# Scheme.net
KiCad netlist of a schematic drawn in Altium Designer
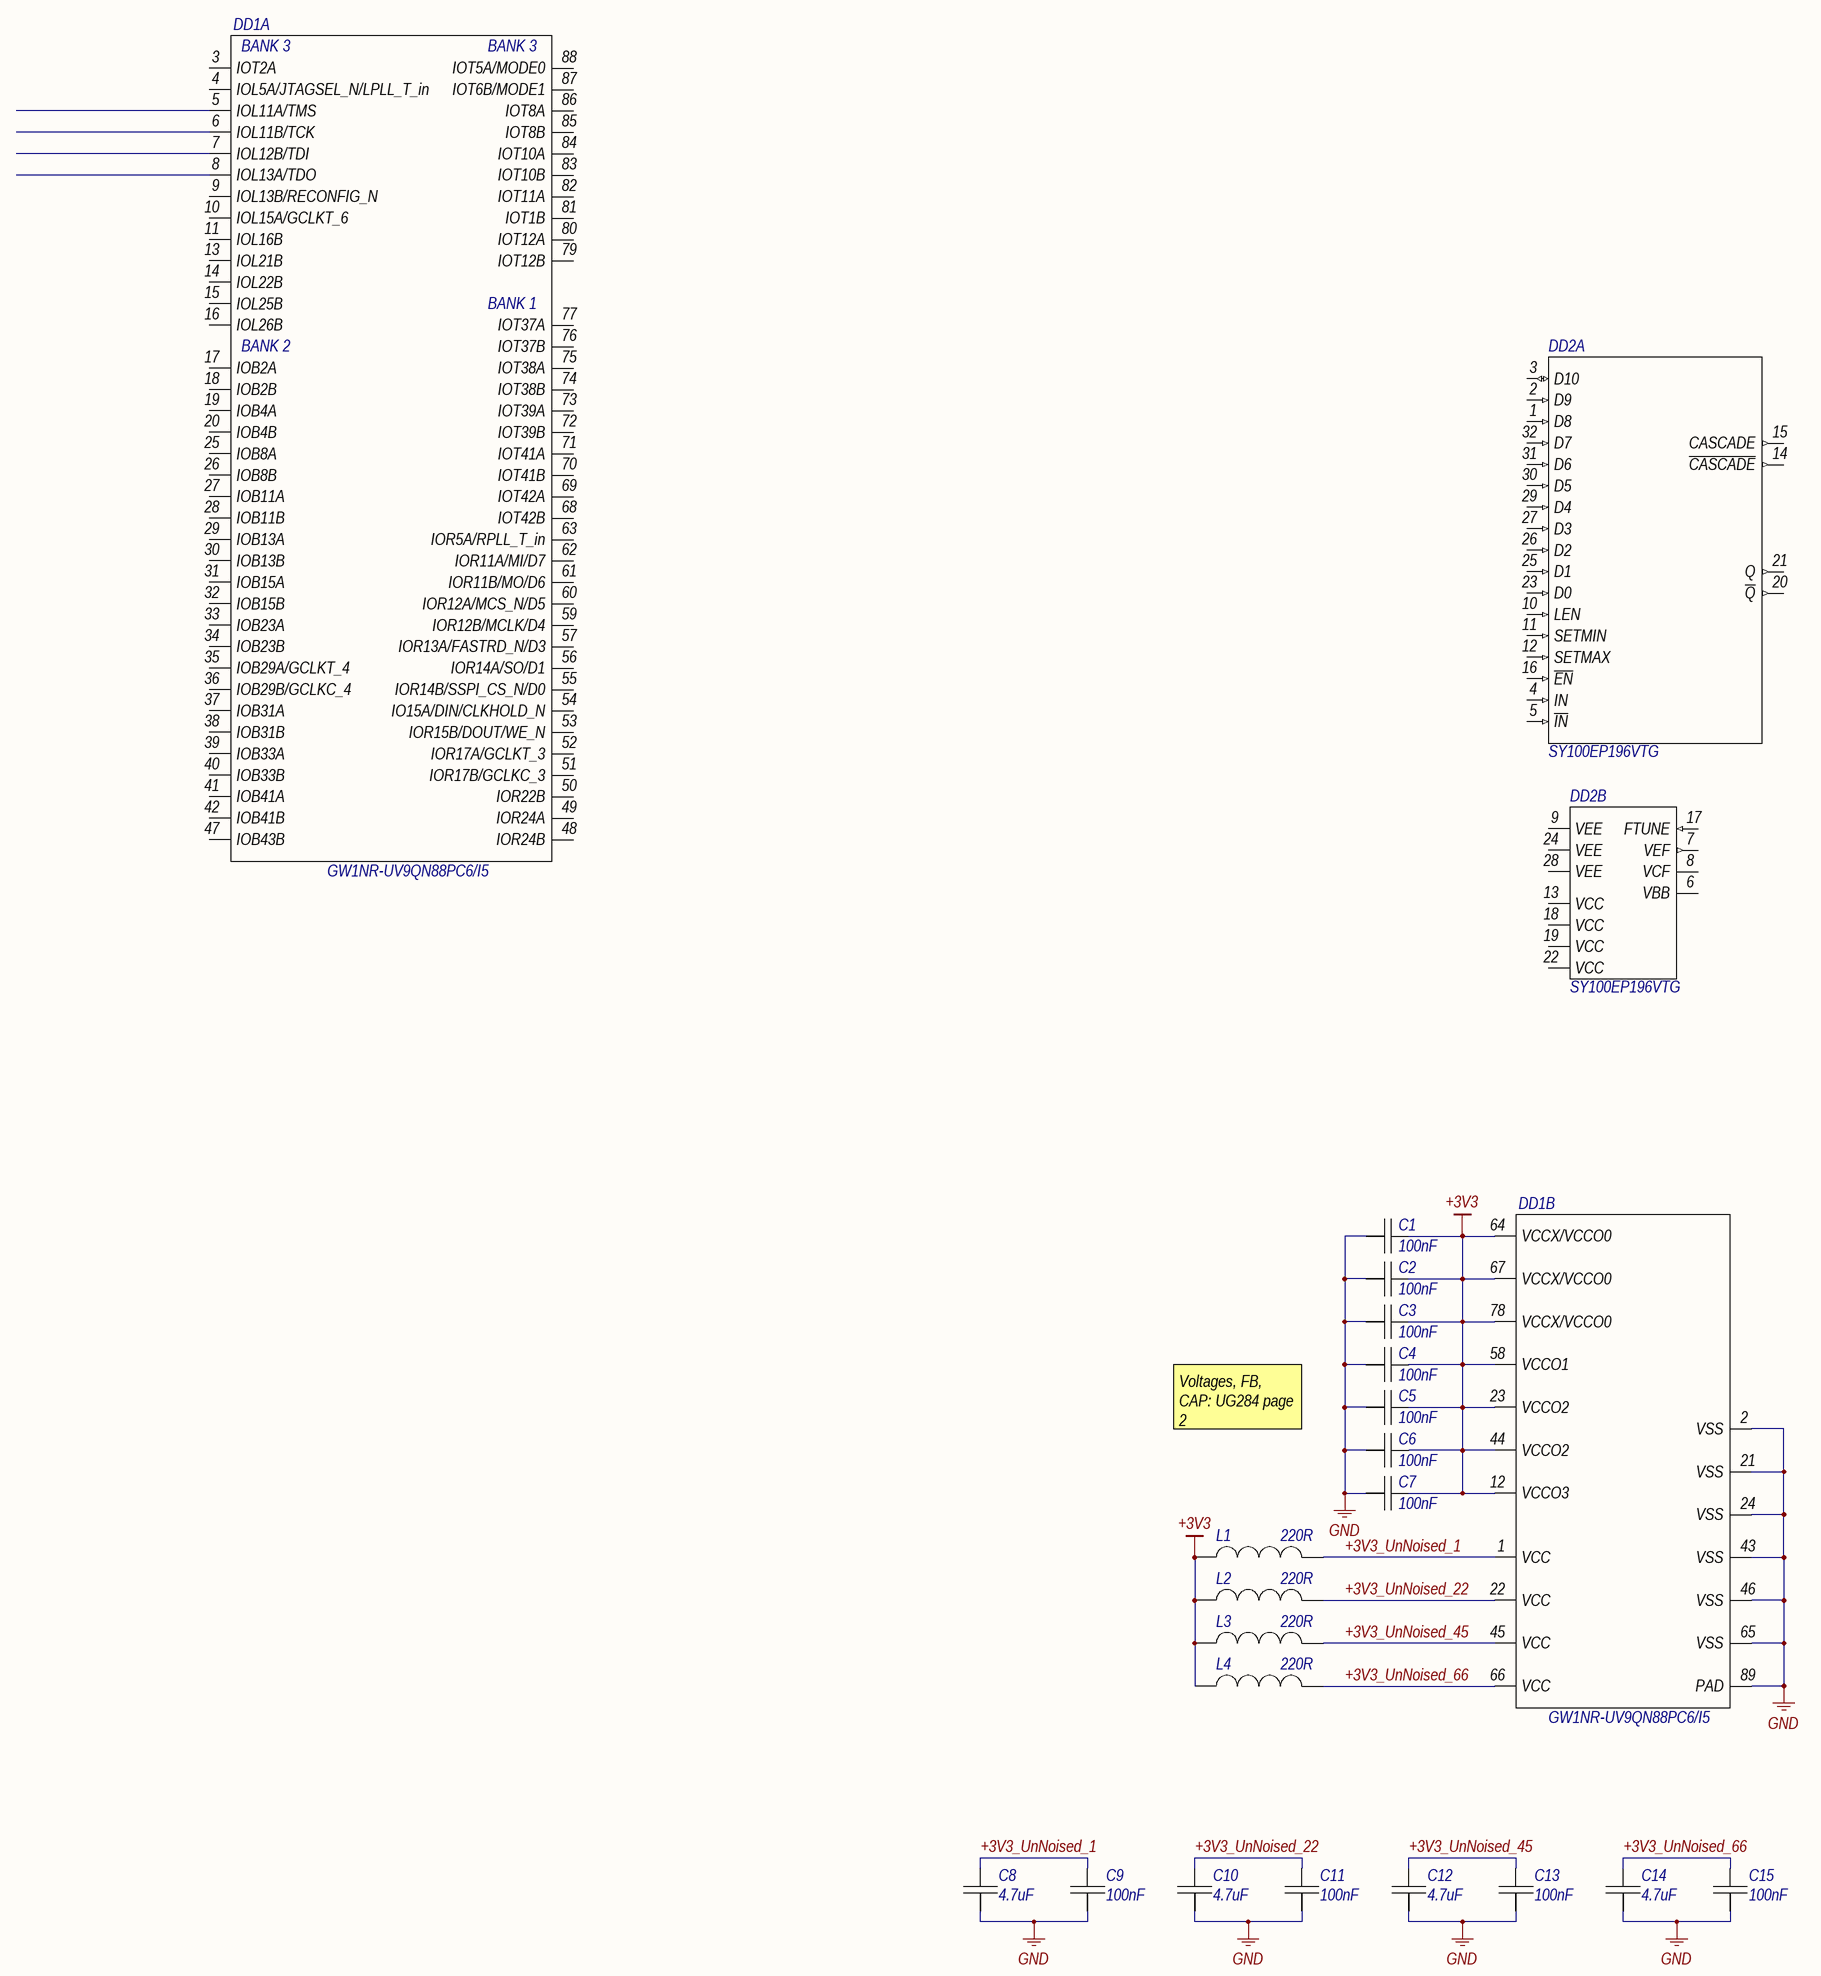
[diagram p0: Scheme.SchDoc]

(export (version "E")
  (design (tool "Eeschema 10.0.6"))
  (components
    (comp (ref "C1")
      (value "100nF")
      (footprint "CAP0402")
      (fields
        (field (name "MANUFACTURER") "Samsung Electro-Mechanics")
        (field (name "MPN") "CL05B104KO5NNNC")
        (field (name "TOLERANCE") "10%")
      )
      (libsource (lib "Library") (part "CAPC"))
    )
    (comp (ref "C2")
      (value "100nF")
      (footprint "CAP0402")
      (fields
        (field (name "MANUFACTURER") "Samsung Electro-Mechanics")
        (field (name "MPN") "CL05B104KO5NNNC")
        (field (name "TOLERANCE") "10%")
      )
      (libsource (lib "Library") (part "CAPC"))
    )
    (comp (ref "C3")
      (value "100nF")
      (footprint "CAP0402")
      (fields
        (field (name "MANUFACTURER") "Samsung Electro-Mechanics")
        (field (name "MPN") "CL05B104KO5NNNC")
        (field (name "TOLERANCE") "10%")
      )
      (libsource (lib "Library") (part "CAPC"))
    )
    (comp (ref "C4")
      (value "100nF")
      (footprint "CAP0402")
      (fields
        (field (name "MANUFACTURER") "Samsung Electro-Mechanics")
        (field (name "MPN") "CL05B104KO5NNNC")
        (field (name "TOLERANCE") "10%")
      )
      (libsource (lib "Library") (part "CAPC"))
    )
    (comp (ref "C5")
      (value "100nF")
      (footprint "CAP0402")
      (fields
        (field (name "MANUFACTURER") "Samsung Electro-Mechanics")
        (field (name "MPN") "CL05B104KO5NNNC")
        (field (name "TOLERANCE") "10%")
      )
      (libsource (lib "Library") (part "CAPC"))
    )
    (comp (ref "C6")
      (value "100nF")
      (footprint "CAP0402")
      (fields
        (field (name "MANUFACTURER") "Samsung Electro-Mechanics")
        (field (name "MPN") "CL05B104KO5NNNC")
        (field (name "TOLERANCE") "10%")
      )
      (libsource (lib "Library") (part "CAPC"))
    )
    (comp (ref "C7")
      (value "100nF")
      (footprint "CAP0402")
      (fields
        (field (name "MANUFACTURER") "Samsung Electro-Mechanics")
        (field (name "MPN") "CL05B104KO5NNNC")
        (field (name "TOLERANCE") "10%")
      )
      (libsource (lib "Library") (part "CAPC"))
    )
    (comp (ref "C8")
      (value "4.7uF")
      (footprint "CAP0402")
      (fields
        (field (name "MANUFACTURER") "Samsung Electro-Mechanics")
        (field (name "MPN") "CL05A475MP5NRNC")
        (field (name "TOLERANCE") "20%")
      )
      (libsource (lib "Library") (part "CAPC"))
    )
    (comp (ref "C9")
      (value "100nF")
      (footprint "CAP0402")
      (fields
        (field (name "MANUFACTURER") "Samsung Electro-Mechanics")
        (field (name "MPN") "CL05B104KO5NNNC")
        (field (name "TOLERANCE") "10%")
      )
      (libsource (lib "Library") (part "CAPC"))
    )
    (comp (ref "C10")
      (value "4.7uF")
      (footprint "CAP0402")
      (fields
        (field (name "MANUFACTURER") "Samsung Electro-Mechanics")
        (field (name "MPN") "CL05A475MP5NRNC")
        (field (name "TOLERANCE") "20%")
      )
      (libsource (lib "Library") (part "CAPC"))
    )
    (comp (ref "C11")
      (value "100nF")
      (footprint "CAP0402")
      (fields
        (field (name "MANUFACTURER") "Samsung Electro-Mechanics")
        (field (name "MPN") "CL05B104KO5NNNC")
        (field (name "TOLERANCE") "10%")
      )
      (libsource (lib "Library") (part "CAPC"))
    )
    (comp (ref "C12")
      (value "4.7uF")
      (footprint "CAP0402")
      (fields
        (field (name "MANUFACTURER") "Samsung Electro-Mechanics")
        (field (name "MPN") "CL05A475MP5NRNC")
        (field (name "TOLERANCE") "20%")
      )
      (libsource (lib "Library") (part "CAPC"))
    )
    (comp (ref "C13")
      (value "100nF")
      (footprint "CAP0402")
      (fields
        (field (name "MANUFACTURER") "Samsung Electro-Mechanics")
        (field (name "MPN") "CL05B104KO5NNNC")
        (field (name "TOLERANCE") "10%")
      )
      (libsource (lib "Library") (part "CAPC"))
    )
    (comp (ref "C14")
      (value "4.7uF")
      (footprint "CAP0402")
      (fields
        (field (name "MANUFACTURER") "Samsung Electro-Mechanics")
        (field (name "MPN") "CL05A475MP5NRNC")
        (field (name "TOLERANCE") "20%")
      )
      (libsource (lib "Library") (part "CAPC"))
    )
    (comp (ref "C15")
      (value "100nF")
      (footprint "CAP0402")
      (fields
        (field (name "MANUFACTURER") "Samsung Electro-Mechanics")
        (field (name "MPN") "CL05B104KO5NNNC")
        (field (name "TOLERANCE") "10%")
      )
      (libsource (lib "Library") (part "CAPC"))
    )
    (comp (ref "DD1")
      (value "GW1NR-UV9QN88PC6/I5")
      (footprint "QFN88_0.4pitch")
      (fields (field (name "MPN") "GW1NR-UV9QN88PC6/I5") (field (name "MANUFACTURER") "GoWin"))
      (libsource (lib "Library") (part "DD_GW1NR-UV9QN88PC6/I5"))
    )
    (comp (ref "DD2")
      (value "~")
      (footprint "TQFP-32_M")
      (fields
        (field (name "MPN") "SY100EP196VTG")
        (field (name "PART NUMBER") "SY100EP196VTG")
        (field (name "MANUFACTURER") "Microchip")
      )
      (libsource (lib "Library") (part "SY100EP196VTG"))
    )
    (comp (ref "L1")
      (value "220R")
      (footprint "CAPC0603N")
      (fields
        (field (name "MANUFACTURER") "Murata Electronics")
        (field (name "MPN") "BLM18KG221SN1D")
        (field (name "TOLERANCE") "25%")
      )
      (libsource (lib "Library") (part "Inductor"))
    )
    (comp (ref "L2")
      (value "220R")
      (footprint "CAPC0603N")
      (fields
        (field (name "MANUFACTURER") "Murata Electronics")
        (field (name "MPN") "BLM18KG221SN1D")
        (field (name "TOLERANCE") "25%")
      )
      (libsource (lib "Library") (part "Inductor"))
    )
    (comp (ref "L3")
      (value "220R")
      (footprint "CAPC0603N")
      (fields
        (field (name "MANUFACTURER") "Murata Electronics")
        (field (name "MPN") "BLM18KG221SN1D")
        (field (name "TOLERANCE") "25%")
      )
      (libsource (lib "Library") (part "Inductor"))
    )
    (comp (ref "L4")
      (value "220R")
      (footprint "CAPC0603N")
      (fields
        (field (name "MANUFACTURER") "Murata Electronics")
        (field (name "MPN") "BLM18KG221SN1D")
        (field (name "TOLERANCE") "25%")
      )
      (libsource (lib "Library") (part "Inductor"))
    )
  )
  (nets
    (net (code "1") (name "+3V3") (class "Default")
      (node (ref "C1") (pin "2") (pinfunction "2_2") (pintype "passive"))
      (node (ref "C2") (pin "2") (pinfunction "2_2") (pintype "passive"))
      (node (ref "C3") (pin "2") (pinfunction "2_2") (pintype "passive"))
      (node (ref "C4") (pin "2") (pinfunction "2_2") (pintype "passive"))
      (node (ref "C5") (pin "2") (pinfunction "2_2") (pintype "passive"))
      (node (ref "C6") (pin "2") (pinfunction "2_2") (pintype "passive"))
      (node (ref "C7") (pin "2") (pinfunction "2_2") (pintype "passive"))
      (node (ref "DD1") (pin "12") (pinfunction "VCCO3_12") (pintype "power_in"))
      (node (ref "DD1") (pin "23") (pinfunction "VCCO2_23") (pintype "power_in"))
      (node (ref "DD1") (pin "44") (pinfunction "VCCO2_44") (pintype "power_in"))
      (node (ref "DD1") (pin "58") (pinfunction "VCCO1_58") (pintype "power_in"))
      (node (ref "DD1") (pin "64") (pinfunction "VCCX/VCCO0_64") (pintype "power_in"))
      (node (ref "DD1") (pin "67") (pinfunction "VCCX/VCCO0_67") (pintype "power_in"))
      (node (ref "DD1") (pin "78") (pinfunction "VCCX/VCCO0_78") (pintype "power_in"))
      (node (ref "L1") (pin "1") (pinfunction "1_1") (pintype "passive"))
      (node (ref "L2") (pin "1") (pinfunction "1_1") (pintype "passive"))
      (node (ref "L3") (pin "1") (pinfunction "1_1") (pintype "passive"))
      (node (ref "L4") (pin "1") (pinfunction "1_1") (pintype "passive"))
    )
    (net (code "2") (name "/+3V3_UnNoised_1") (class "Default")
      (node (ref "C8") (pin "2") (pinfunction "2_2") (pintype "passive"))
      (node (ref "C9") (pin "2") (pinfunction "2_2") (pintype "passive"))
      (node (ref "DD1") (pin "1") (pinfunction "VCC_1") (pintype "power_in"))
      (node (ref "L1") (pin "2") (pinfunction "2_2") (pintype "passive"))
    )
    (net (code "3") (name "/+3V3_UnNoised_22") (class "Default")
      (node (ref "C10") (pin "2") (pinfunction "2_2") (pintype "passive"))
      (node (ref "C11") (pin "2") (pinfunction "2_2") (pintype "passive"))
      (node (ref "DD1") (pin "22") (pinfunction "VCC_22") (pintype "power_in"))
      (node (ref "L2") (pin "2") (pinfunction "2_2") (pintype "passive"))
    )
    (net (code "4") (name "/+3V3_UnNoised_45") (class "Default")
      (node (ref "C12") (pin "2") (pinfunction "2_2") (pintype "passive"))
      (node (ref "C13") (pin "2") (pinfunction "2_2") (pintype "passive"))
      (node (ref "DD1") (pin "45") (pinfunction "VCC_45") (pintype "power_in"))
      (node (ref "L3") (pin "2") (pinfunction "2_2") (pintype "passive"))
    )
    (net (code "5") (name "/+3V3_UnNoised_66") (class "Default")
      (node (ref "C14") (pin "2") (pinfunction "2_2") (pintype "passive"))
      (node (ref "C15") (pin "2") (pinfunction "2_2") (pintype "passive"))
      (node (ref "DD1") (pin "66") (pinfunction "VCC_66") (pintype "power_in"))
      (node (ref "L4") (pin "2") (pinfunction "2_2") (pintype "passive"))
    )
    (net (code "6") (name "GND") (class "Default")
      (node (ref "C1") (pin "1") (pinfunction "1_1") (pintype "passive"))
      (node (ref "C10") (pin "1") (pinfunction "1_1") (pintype "passive"))
      (node (ref "C11") (pin "1") (pinfunction "1_1") (pintype "passive"))
      (node (ref "C12") (pin "1") (pinfunction "1_1") (pintype "passive"))
      (node (ref "C13") (pin "1") (pinfunction "1_1") (pintype "passive"))
      (node (ref "C14") (pin "1") (pinfunction "1_1") (pintype "passive"))
      (node (ref "C15") (pin "1") (pinfunction "1_1") (pintype "passive"))
      (node (ref "C2") (pin "1") (pinfunction "1_1") (pintype "passive"))
      (node (ref "C3") (pin "1") (pinfunction "1_1") (pintype "passive"))
      (node (ref "C4") (pin "1") (pinfunction "1_1") (pintype "passive"))
      (node (ref "C5") (pin "1") (pinfunction "1_1") (pintype "passive"))
      (node (ref "C6") (pin "1") (pinfunction "1_1") (pintype "passive"))
      (node (ref "C7") (pin "1") (pinfunction "1_1") (pintype "passive"))
      (node (ref "C8") (pin "1") (pinfunction "1_1") (pintype "passive"))
      (node (ref "C9") (pin "1") (pinfunction "1_1") (pintype "passive"))
      (node (ref "DD1") (pin "2") (pinfunction "VSS_2") (pintype "power_in"))
      (node (ref "DD1") (pin "21") (pinfunction "VSS_21") (pintype "power_in"))
      (node (ref "DD1") (pin "24") (pinfunction "VSS_24") (pintype "power_in"))
      (node (ref "DD1") (pin "43") (pinfunction "VSS_43") (pintype "power_in"))
      (node (ref "DD1") (pin "46") (pinfunction "VSS_46") (pintype "power_in"))
      (node (ref "DD1") (pin "65") (pinfunction "VSS_65") (pintype "power_in"))
      (node (ref "DD1") (pin "89") (pinfunction "PAD_89") (pintype "passive"))
    )
    (net (code "7") (name "unconnected-(DD1A-IO15A{slash}DIN{slash}CLKHOLD_N-Pad54)") (class "Default")
      (node (ref "DD1") (pin "54") (pinfunction "IO15A/DIN/CLKHOLD_N_54") (pintype "passive"))
    )
    (net (code "8") (name "unconnected-(DD1A-IOB2A-Pad17)") (class "Default")
      (node (ref "DD1") (pin "17") (pinfunction "IOB2A_17") (pintype "passive"))
    )
    (net (code "9") (name "unconnected-(DD1A-IOB2B-Pad18)") (class "Default")
      (node (ref "DD1") (pin "18") (pinfunction "IOB2B_18") (pintype "passive"))
    )
    (net (code "10") (name "unconnected-(DD1A-IOB4A-Pad19)") (class "Default")
      (node (ref "DD1") (pin "19") (pinfunction "IOB4A_19") (pintype "passive"))
    )
    (net (code "11") (name "unconnected-(DD1A-IOB4B-Pad20)") (class "Default")
      (node (ref "DD1") (pin "20") (pinfunction "IOB4B_20") (pintype "passive"))
    )
    (net (code "12") (name "unconnected-(DD1A-IOB8A-Pad25)") (class "Default")
      (node (ref "DD1") (pin "25") (pinfunction "IOB8A_25") (pintype "passive"))
    )
    (net (code "13") (name "unconnected-(DD1A-IOB8B-Pad26)") (class "Default")
      (node (ref "DD1") (pin "26") (pinfunction "IOB8B_26") (pintype "passive"))
    )
    (net (code "14") (name "unconnected-(DD1A-IOB11A-Pad27)") (class "Default")
      (node (ref "DD1") (pin "27") (pinfunction "IOB11A_27") (pintype "passive"))
    )
    (net (code "15") (name "unconnected-(DD1A-IOB11B-Pad28)") (class "Default")
      (node (ref "DD1") (pin "28") (pinfunction "IOB11B_28") (pintype "passive"))
    )
    (net (code "16") (name "unconnected-(DD1A-IOB13A-Pad29)") (class "Default")
      (node (ref "DD1") (pin "29") (pinfunction "IOB13A_29") (pintype "passive"))
    )
    (net (code "17") (name "unconnected-(DD1A-IOB13B-Pad30)") (class "Default")
      (node (ref "DD1") (pin "30") (pinfunction "IOB13B_30") (pintype "passive"))
    )
    (net (code "18") (name "unconnected-(DD1A-IOB15A-Pad31)") (class "Default")
      (node (ref "DD1") (pin "31") (pinfunction "IOB15A_31") (pintype "passive"))
    )
    (net (code "19") (name "unconnected-(DD1A-IOB15B-Pad32)") (class "Default")
      (node (ref "DD1") (pin "32") (pinfunction "IOB15B_32") (pintype "passive"))
    )
    (net (code "20") (name "unconnected-(DD1A-IOB23A-Pad33)") (class "Default")
      (node (ref "DD1") (pin "33") (pinfunction "IOB23A_33") (pintype "passive"))
    )
    (net (code "21") (name "unconnected-(DD1A-IOB23B-Pad34)") (class "Default")
      (node (ref "DD1") (pin "34") (pinfunction "IOB23B_34") (pintype "passive"))
    )
    (net (code "22") (name "unconnected-(DD1A-IOB29A{slash}GCLKT_4-Pad35)") (class "Default")
      (node (ref "DD1") (pin "35") (pinfunction "IOB29A/GCLKT_4_35") (pintype "passive"))
    )
    (net (code "23") (name "unconnected-(DD1A-IOB29B{slash}GCLKC_4-Pad36)") (class "Default")
      (node (ref "DD1") (pin "36") (pinfunction "IOB29B/GCLKC_4_36") (pintype "passive"))
    )
    (net (code "24") (name "unconnected-(DD1A-IOB31A-Pad37)") (class "Default")
      (node (ref "DD1") (pin "37") (pinfunction "IOB31A_37") (pintype "passive"))
    )
    (net (code "25") (name "unconnected-(DD1A-IOB31B-Pad38)") (class "Default")
      (node (ref "DD1") (pin "38") (pinfunction "IOB31B_38") (pintype "passive"))
    )
    (net (code "26") (name "unconnected-(DD1A-IOB33A-Pad39)") (class "Default")
      (node (ref "DD1") (pin "39") (pinfunction "IOB33A_39") (pintype "passive"))
    )
    (net (code "27") (name "unconnected-(DD1A-IOB33B-Pad40)") (class "Default")
      (node (ref "DD1") (pin "40") (pinfunction "IOB33B_40") (pintype "passive"))
    )
    (net (code "28") (name "unconnected-(DD1A-IOB41A-Pad41)") (class "Default")
      (node (ref "DD1") (pin "41") (pinfunction "IOB41A_41") (pintype "passive"))
    )
    (net (code "29") (name "unconnected-(DD1A-IOB41B-Pad42)") (class "Default")
      (node (ref "DD1") (pin "42") (pinfunction "IOB41B_42") (pintype "passive"))
    )
    (net (code "30") (name "unconnected-(DD1A-IOB43B-Pad47)") (class "Default")
      (node (ref "DD1") (pin "47") (pinfunction "IOB43B_47") (pintype "passive"))
    )
    (net (code "31") (name "unconnected-(DD1A-IOL5A{slash}JTAGSEL_N{slash}LPLL_T_in-Pad4)") (class "Default")
      (node (ref "DD1") (pin "4") (pinfunction "IOL5A/JTAGSEL_N/LPLL_T_in_4") (pintype "passive"))
    )
    (net (code "32") (name "unconnected-(DD1A-IOL11A{slash}TMS-Pad5)") (class "Default")
      (node (ref "DD1") (pin "5") (pinfunction "IOL11A/TMS_5") (pintype "passive"))
    )
    (net (code "33") (name "unconnected-(DD1A-IOL11B{slash}TCK-Pad6)") (class "Default")
      (node (ref "DD1") (pin "6") (pinfunction "IOL11B/TCK_6") (pintype "passive"))
    )
    (net (code "34") (name "unconnected-(DD1A-IOL12B{slash}TDI-Pad7)") (class "Default")
      (node (ref "DD1") (pin "7") (pinfunction "IOL12B/TDI_7") (pintype "passive"))
    )
    (net (code "35") (name "unconnected-(DD1A-IOL13A{slash}TDO-Pad8)") (class "Default")
      (node (ref "DD1") (pin "8") (pinfunction "IOL13A/TDO_8") (pintype "passive"))
    )
    (net (code "36") (name "unconnected-(DD1A-IOL13B{slash}RECONFIG_N-Pad9)") (class "Default")
      (node (ref "DD1") (pin "9") (pinfunction "IOL13B/RECONFIG_N_9") (pintype "passive"))
    )
    (net (code "37") (name "unconnected-(DD1A-IOL15A{slash}GCLKT_6-Pad10)") (class "Default")
      (node (ref "DD1") (pin "10") (pinfunction "IOL15A/GCLKT_6_10") (pintype "passive"))
    )
    (net (code "38") (name "unconnected-(DD1A-IOL16B-Pad11)") (class "Default")
      (node (ref "DD1") (pin "11") (pinfunction "IOL16B_11") (pintype "passive"))
    )
    (net (code "39") (name "unconnected-(DD1A-IOL21B-Pad13)") (class "Default")
      (node (ref "DD1") (pin "13") (pinfunction "IOL21B_13") (pintype "passive"))
    )
    (net (code "40") (name "unconnected-(DD1A-IOL22B-Pad14)") (class "Default")
      (node (ref "DD1") (pin "14") (pinfunction "IOL22B_14") (pintype "passive"))
    )
    (net (code "41") (name "unconnected-(DD1A-IOL25B-Pad15)") (class "Default")
      (node (ref "DD1") (pin "15") (pinfunction "IOL25B_15") (pintype "passive"))
    )
    (net (code "42") (name "unconnected-(DD1A-IOL26B-Pad16)") (class "Default")
      (node (ref "DD1") (pin "16") (pinfunction "IOL26B_16") (pintype "passive"))
    )
    (net (code "43") (name "unconnected-(DD1A-IOR5A{slash}RPLL_T_in-Pad63)") (class "Default")
      (node (ref "DD1") (pin "63") (pinfunction "IOR5A/RPLL_T_in_63") (pintype "passive"))
    )
    (net (code "44") (name "unconnected-(DD1A-IOR11A{slash}MI{slash}D7-Pad62)") (class "Default")
      (node (ref "DD1") (pin "62") (pinfunction "IOR11A/MI/D7_62") (pintype "passive"))
    )
    (net (code "45") (name "unconnected-(DD1A-IOR11B{slash}MO{slash}D6-Pad61)") (class "Default")
      (node (ref "DD1") (pin "61") (pinfunction "IOR11B/MO/D6_61") (pintype "passive"))
    )
    (net (code "46") (name "unconnected-(DD1A-IOR12A{slash}MCS_N{slash}D5-Pad60)") (class "Default")
      (node (ref "DD1") (pin "60") (pinfunction "IOR12A/MCS_N/D5_60") (pintype "passive"))
    )
    (net (code "47") (name "unconnected-(DD1A-IOR12B{slash}MCLK{slash}D4-Pad59)") (class "Default")
      (node (ref "DD1") (pin "59") (pinfunction "IOR12B/MCLK/D4_59") (pintype "passive"))
    )
    (net (code "48") (name "unconnected-(DD1A-IOR13A{slash}FASTRD_N{slash}D3-Pad57)") (class "Default")
      (node (ref "DD1") (pin "57") (pinfunction "IOR13A/FASTRD_N/D3_57") (pintype "passive"))
    )
    (net (code "49") (name "unconnected-(DD1A-IOR14A{slash}SO{slash}D1-Pad56)") (class "Default")
      (node (ref "DD1") (pin "56") (pinfunction "IOR14A/SO/D1_56") (pintype "passive"))
    )
    (net (code "50") (name "unconnected-(DD1A-IOR14B{slash}SSPI_CS_N{slash}D0-Pad55)") (class "Default")
      (node (ref "DD1") (pin "55") (pinfunction "IOR14B/SSPI_CS_N/D0_55") (pintype "passive"))
    )
    (net (code "51") (name "unconnected-(DD1A-IOR15B{slash}DOUT{slash}WE_N-Pad53)") (class "Default")
      (node (ref "DD1") (pin "53") (pinfunction "IOR15B/DOUT/WE_N_53") (pintype "passive"))
    )
    (net (code "52") (name "unconnected-(DD1A-IOR17A{slash}GCLKT_3-Pad52)") (class "Default")
      (node (ref "DD1") (pin "52") (pinfunction "IOR17A/GCLKT_3_52") (pintype "passive"))
    )
    (net (code "53") (name "unconnected-(DD1A-IOR17B{slash}GCLKC_3-Pad51)") (class "Default")
      (node (ref "DD1") (pin "51") (pinfunction "IOR17B/GCLKC_3_51") (pintype "passive"))
    )
    (net (code "54") (name "unconnected-(DD1A-IOR22B-Pad50)") (class "Default")
      (node (ref "DD1") (pin "50") (pinfunction "IOR22B_50") (pintype "passive"))
    )
    (net (code "55") (name "unconnected-(DD1A-IOR24A-Pad49)") (class "Default")
      (node (ref "DD1") (pin "49") (pinfunction "IOR24A_49") (pintype "passive"))
    )
    (net (code "56") (name "unconnected-(DD1A-IOR24B-Pad48)") (class "Default")
      (node (ref "DD1") (pin "48") (pinfunction "IOR24B_48") (pintype "passive"))
    )
    (net (code "57") (name "unconnected-(DD1A-IOT1B-Pad81)") (class "Default")
      (node (ref "DD1") (pin "81") (pinfunction "IOT1B_81") (pintype "passive"))
    )
    (net (code "58") (name "unconnected-(DD1A-IOT2A-Pad3)") (class "Default")
      (node (ref "DD1") (pin "3") (pinfunction "IOT2A_3") (pintype "passive"))
    )
    (net (code "59") (name "unconnected-(DD1A-IOT5A{slash}MODE0-Pad88)") (class "Default")
      (node (ref "DD1") (pin "88") (pinfunction "IOT5A/MODE0_88") (pintype "passive"))
    )
    (net (code "60") (name "unconnected-(DD1A-IOT6B{slash}MODE1-Pad87)") (class "Default")
      (node (ref "DD1") (pin "87") (pinfunction "IOT6B/MODE1_87") (pintype "passive"))
    )
    (net (code "61") (name "unconnected-(DD1A-IOT8A-Pad86)") (class "Default")
      (node (ref "DD1") (pin "86") (pinfunction "IOT8A_86") (pintype "passive"))
    )
    (net (code "62") (name "unconnected-(DD1A-IOT8B-Pad85)") (class "Default")
      (node (ref "DD1") (pin "85") (pinfunction "IOT8B_85") (pintype "passive"))
    )
    (net (code "63") (name "unconnected-(DD1A-IOT10A-Pad84)") (class "Default")
      (node (ref "DD1") (pin "84") (pinfunction "IOT10A_84") (pintype "passive"))
    )
    (net (code "64") (name "unconnected-(DD1A-IOT10B-Pad83)") (class "Default")
      (node (ref "DD1") (pin "83") (pinfunction "IOT10B_83") (pintype "passive"))
    )
    (net (code "65") (name "unconnected-(DD1A-IOT11A-Pad82)") (class "Default")
      (node (ref "DD1") (pin "82") (pinfunction "IOT11A_82") (pintype "passive"))
    )
    (net (code "66") (name "unconnected-(DD1A-IOT12A-Pad80)") (class "Default")
      (node (ref "DD1") (pin "80") (pinfunction "IOT12A_80") (pintype "passive"))
    )
    (net (code "67") (name "unconnected-(DD1A-IOT12B-Pad79)") (class "Default")
      (node (ref "DD1") (pin "79") (pinfunction "IOT12B_79") (pintype "passive"))
    )
    (net (code "68") (name "unconnected-(DD1A-IOT37A-Pad77)") (class "Default")
      (node (ref "DD1") (pin "77") (pinfunction "IOT37A_77") (pintype "passive"))
    )
    (net (code "69") (name "unconnected-(DD1A-IOT37B-Pad76)") (class "Default")
      (node (ref "DD1") (pin "76") (pinfunction "IOT37B_76") (pintype "passive"))
    )
    (net (code "70") (name "unconnected-(DD1A-IOT38A-Pad75)") (class "Default")
      (node (ref "DD1") (pin "75") (pinfunction "IOT38A_75") (pintype "passive"))
    )
    (net (code "71") (name "unconnected-(DD1A-IOT38B-Pad74)") (class "Default")
      (node (ref "DD1") (pin "74") (pinfunction "IOT38B_74") (pintype "passive"))
    )
    (net (code "72") (name "unconnected-(DD1A-IOT39A-Pad73)") (class "Default")
      (node (ref "DD1") (pin "73") (pinfunction "IOT39A_73") (pintype "passive"))
    )
    (net (code "73") (name "unconnected-(DD1A-IOT39B-Pad72)") (class "Default")
      (node (ref "DD1") (pin "72") (pinfunction "IOT39B_72") (pintype "passive"))
    )
    (net (code "74") (name "unconnected-(DD1A-IOT41A-Pad71)") (class "Default")
      (node (ref "DD1") (pin "71") (pinfunction "IOT41A_71") (pintype "passive"))
    )
    (net (code "75") (name "unconnected-(DD1A-IOT41B-Pad70)") (class "Default")
      (node (ref "DD1") (pin "70") (pinfunction "IOT41B_70") (pintype "passive"))
    )
    (net (code "76") (name "unconnected-(DD1A-IOT42A-Pad69)") (class "Default")
      (node (ref "DD1") (pin "69") (pinfunction "IOT42A_69") (pintype "passive"))
    )
    (net (code "77") (name "unconnected-(DD1A-IOT42B-Pad68)") (class "Default")
      (node (ref "DD1") (pin "68") (pinfunction "IOT42B_68") (pintype "passive"))
    )
    (net (code "78") (name "unconnected-(DD2A-CASCADE-Pad15)") (class "Default")
      (node (ref "DD2") (pin "15") (pinfunction "CASCADE_15") (pintype "output"))
    )
    (net (code "79") (name "unconnected-(DD2A-D0-Pad23)") (class "Default")
      (node (ref "DD2") (pin "23") (pinfunction "D0_23") (pintype "input"))
    )
    (net (code "80") (name "unconnected-(DD2A-D1-Pad25)") (class "Default")
      (node (ref "DD2") (pin "25") (pinfunction "D1_25") (pintype "input"))
    )
    (net (code "81") (name "unconnected-(DD2A-D2-Pad26)") (class "Default")
      (node (ref "DD2") (pin "26") (pinfunction "D2_26") (pintype "input"))
    )
    (net (code "82") (name "unconnected-(DD2A-D3-Pad27)") (class "Default")
      (node (ref "DD2") (pin "27") (pinfunction "D3_27") (pintype "input"))
    )
    (net (code "83") (name "unconnected-(DD2A-D4-Pad29)") (class "Default")
      (node (ref "DD2") (pin "29") (pinfunction "D4_29") (pintype "input"))
    )
    (net (code "84") (name "unconnected-(DD2A-D5-Pad30)") (class "Default")
      (node (ref "DD2") (pin "30") (pinfunction "D5_30") (pintype "input"))
    )
    (net (code "85") (name "unconnected-(DD2A-D6-Pad31)") (class "Default")
      (node (ref "DD2") (pin "31") (pinfunction "D6_31") (pintype "input"))
    )
    (net (code "86") (name "unconnected-(DD2A-D7-Pad32)") (class "Default")
      (node (ref "DD2") (pin "32") (pinfunction "D7_32") (pintype "input"))
    )
    (net (code "87") (name "unconnected-(DD2A-D8-Pad1)") (class "Default")
      (node (ref "DD2") (pin "1") (pinfunction "D8_1") (pintype "input"))
    )
    (net (code "88") (name "unconnected-(DD2A-D9-Pad2)") (class "Default")
      (node (ref "DD2") (pin "2") (pinfunction "D9_2") (pintype "input"))
    )
    (net (code "89") (name "unconnected-(DD2A-D10-Pad3)") (class "Default")
      (node (ref "DD2") (pin "3") (pinfunction "D10_3") (pintype "bidirectional"))
    )
    (net (code "90") (name "unconnected-(DD2A-IN-Pad4)") (class "Default")
      (node (ref "DD2") (pin "4") (pinfunction "IN_4") (pintype "input"))
    )
    (net (code "91") (name "unconnected-(DD2A-LEN-Pad10)") (class "Default")
      (node (ref "DD2") (pin "10") (pinfunction "LEN_10") (pintype "input"))
    )
    (net (code "92") (name "unconnected-(DD2A-Q-Pad21)") (class "Default")
      (node (ref "DD2") (pin "21") (pinfunction "Q_21") (pintype "output"))
    )
    (net (code "93") (name "unconnected-(DD2A-SETMAX-Pad12)") (class "Default")
      (node (ref "DD2") (pin "12") (pinfunction "SETMAX_12") (pintype "input"))
    )
    (net (code "94") (name "unconnected-(DD2A-SETMIN-Pad11)") (class "Default")
      (node (ref "DD2") (pin "11") (pinfunction "SETMIN_11") (pintype "input"))
    )
    (net (code "95") (name "unconnected-(DD2A-~{CASCADE}-Pad14)") (class "Default")
      (node (ref "DD2") (pin "14") (pinfunction "~{CASCADE}_14") (pintype "output"))
    )
    (net (code "96") (name "unconnected-(DD2A-~{EN}-Pad16)") (class "Default")
      (node (ref "DD2") (pin "16") (pinfunction "~{EN}_16") (pintype "input"))
    )
    (net (code "97") (name "unconnected-(DD2A-~{IN}-Pad5)") (class "Default")
      (node (ref "DD2") (pin "5") (pinfunction "~{IN}_5") (pintype "input"))
    )
    (net (code "98") (name "unconnected-(DD2A-~{Q}-Pad20)") (class "Default")
      (node (ref "DD2") (pin "20") (pinfunction "~{Q}_20") (pintype "output"))
    )
    (net (code "99") (name "unconnected-(DD2B-FTUNE-Pad17)") (class "Default")
      (node (ref "DD2") (pin "17") (pinfunction "FTUNE_17") (pintype "input"))
    )
    (net (code "100") (name "unconnected-(DD2B-VBB-Pad6)") (class "Default")
      (node (ref "DD2") (pin "6") (pinfunction "VBB_6") (pintype "power_in"))
    )
    (net (code "101") (name "unconnected-(DD2B-VCC-Pad13)") (class "Default")
      (node (ref "DD2") (pin "13") (pinfunction "VCC_13") (pintype "power_in"))
    )
    (net (code "102") (name "unconnected-(DD2B-VCC-Pad18)") (class "Default")
      (node (ref "DD2") (pin "18") (pinfunction "VCC_18") (pintype "power_in"))
    )
    (net (code "103") (name "unconnected-(DD2B-VCC-Pad19)") (class "Default")
      (node (ref "DD2") (pin "19") (pinfunction "VCC_19") (pintype "power_in"))
    )
    (net (code "104") (name "unconnected-(DD2B-VCC-Pad22)") (class "Default")
      (node (ref "DD2") (pin "22") (pinfunction "VCC_22") (pintype "power_in"))
    )
    (net (code "105") (name "unconnected-(DD2B-VCF-Pad8)") (class "Default")
      (node (ref "DD2") (pin "8") (pinfunction "VCF_8") (pintype "power_in"))
    )
    (net (code "106") (name "unconnected-(DD2B-VEE-Pad9)") (class "Default")
      (node (ref "DD2") (pin "9") (pinfunction "VEE_9") (pintype "power_in"))
    )
    (net (code "107") (name "unconnected-(DD2B-VEE-Pad24)") (class "Default")
      (node (ref "DD2") (pin "24") (pinfunction "VEE_24") (pintype "power_in"))
    )
    (net (code "108") (name "unconnected-(DD2B-VEE-Pad28)") (class "Default")
      (node (ref "DD2") (pin "28") (pinfunction "VEE_28") (pintype "power_in"))
    )
    (net (code "109") (name "unconnected-(DD2B-VEF-Pad7)") (class "Default")
      (node (ref "DD2") (pin "7") (pinfunction "VEF_7") (pintype "output"))
    )
  )
)
